# Pi_BISS_422_485.net
KiCad netlist of a schematic drawn in Altium Designer
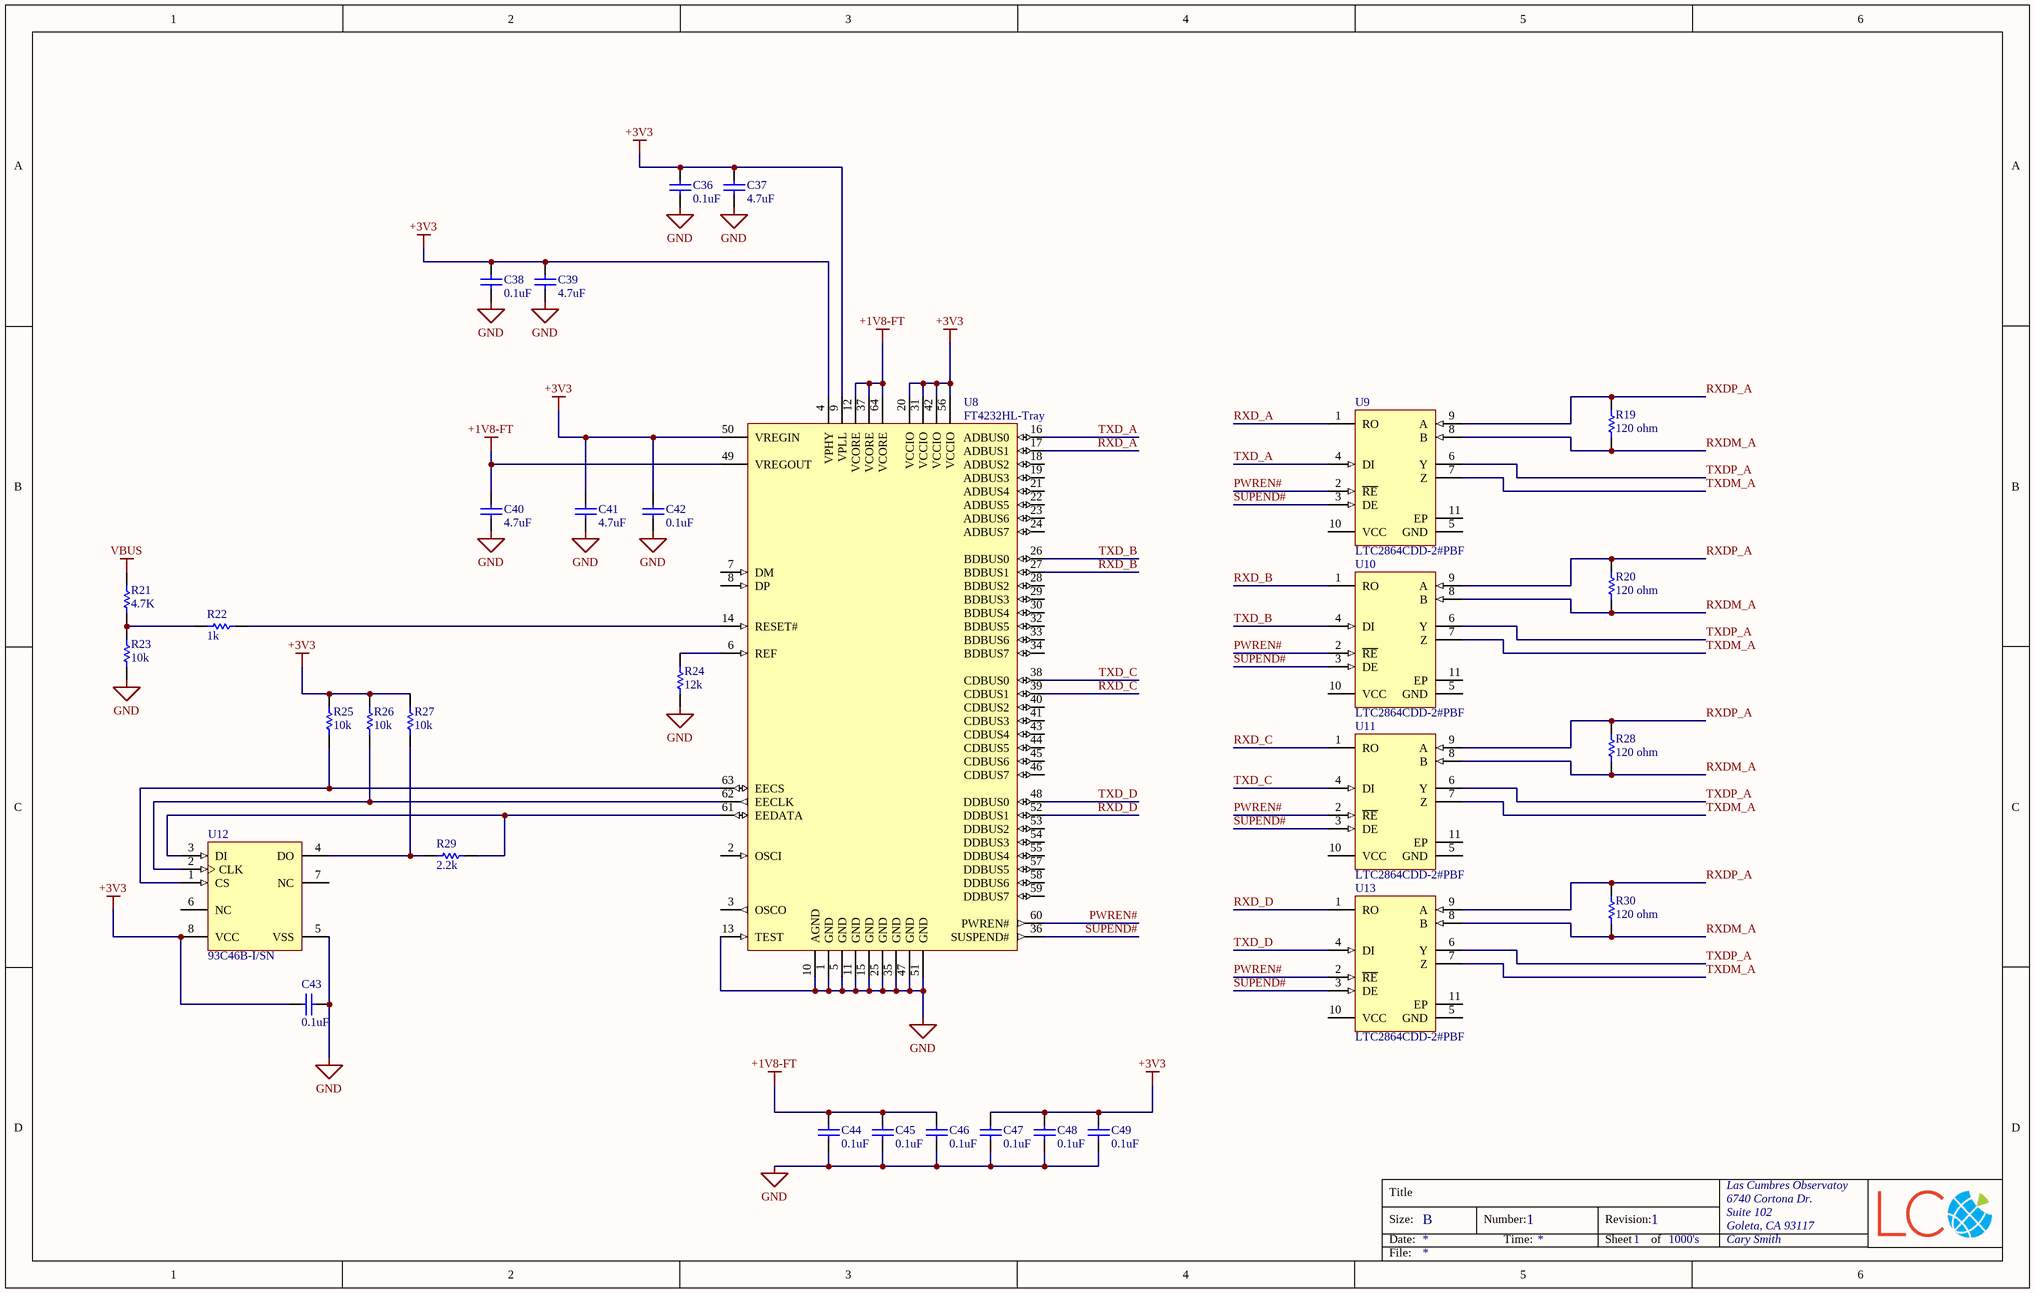
[diagram p0: Pi_BISS_422_485.SchDoc]

(export (version "E")
  (design (tool "Eeschema 10.0.6"))
  (components
    (comp (ref "C36")
      (value "0.1uF")
      (footprint "CAPC1005X55X25ML05T10")
      (description "VJ0402G104KXQCW1BC")
      (fields (field (name "MANUFACTURER") "Vitramon"))
      (libsource (lib "Altium Content Vault") (part "CAP"))
    )
    (comp (ref "C37")
      (value "4.7uF")
      (footprint "CAPC1608X90X35ML10T15")
      (fields (field (name "PARTNUMBER") "GRM188R60J475KE19D") (field (name "TOLERANCE") "10%"))
      (libsource (lib "Altium Content Vault") (part "CAP-NP-2"))
    )
    (comp (ref "C38")
      (value "0.1uF")
      (footprint "CAPC1005X55X25ML05T10")
      (description "VJ0402G104KXQCW1BC")
      (fields (field (name "MANUFACTURER") "Vitramon"))
      (libsource (lib "Altium Content Vault") (part "CAP"))
    )
    (comp (ref "C39")
      (value "4.7uF")
      (footprint "CAPC1608X90X35ML10T15")
      (fields (field (name "PARTNUMBER") "GRM188R60J475KE19D") (field (name "TOLERANCE") "10%"))
      (libsource (lib "Altium Content Vault") (part "CAP-NP-2"))
    )
    (comp (ref "C40")
      (value "4.7uF")
      (footprint "CAPC1608X90X35ML10T15")
      (fields (field (name "PARTNUMBER") "GRM188R60J475KE19D") (field (name "TOLERANCE") "10%"))
      (libsource (lib "Altium Content Vault") (part "CAP-NP-2"))
    )
    (comp (ref "C41")
      (value "4.7uF")
      (footprint "CAPC1608X90X35ML10T15")
      (fields (field (name "PARTNUMBER") "GRM188R60J475KE19D") (field (name "TOLERANCE") "10%"))
      (libsource (lib "Altium Content Vault") (part "CAP-NP-2"))
    )
    (comp (ref "C42")
      (value "0.1uF")
      (footprint "CAPC1005X55X25ML05T10")
      (description "VJ0402G104KXQCW1BC")
      (fields (field (name "MANUFACTURER") "Vitramon"))
      (libsource (lib "Altium Content Vault") (part "CAP"))
    )
    (comp (ref "C43")
      (value "0.1uF")
      (footprint "CAPC1005X55X25ML05T10")
      (description "VJ0402G104KXQCW1BC")
      (fields (field (name "MANUFACTURER") "Vitramon"))
      (libsource (lib "Altium Content Vault") (part "CAP"))
    )
    (comp (ref "C44")
      (value "0.1uF")
      (footprint "CAPC1005X55X25ML05T10")
      (description "VJ0402G104KXQCW1BC")
      (fields (field (name "MANUFACTURER") "Vitramon"))
      (libsource (lib "Altium Content Vault") (part "CAP"))
    )
    (comp (ref "C45")
      (value "0.1uF")
      (footprint "CAPC1005X55X25ML05T10")
      (description "VJ0402G104KXQCW1BC")
      (fields (field (name "MANUFACTURER") "Vitramon"))
      (libsource (lib "Altium Content Vault") (part "CAP"))
    )
    (comp (ref "C46")
      (value "0.1uF")
      (footprint "CAPC1005X55X25ML05T10")
      (description "VJ0402G104KXQCW1BC")
      (fields (field (name "MANUFACTURER") "Vitramon"))
      (libsource (lib "Altium Content Vault") (part "CAP"))
    )
    (comp (ref "C47")
      (value "0.1uF")
      (footprint "CAPC1005X55X25ML05T10")
      (description "VJ0402G104KXQCW1BC")
      (fields (field (name "MANUFACTURER") "Vitramon"))
      (libsource (lib "Altium Content Vault") (part "CAP"))
    )
    (comp (ref "C48")
      (value "0.1uF")
      (footprint "CAPC1005X55X25ML05T10")
      (description "VJ0402G104KXQCW1BC")
      (fields (field (name "MANUFACTURER") "Vitramon"))
      (libsource (lib "Altium Content Vault") (part "CAP"))
    )
    (comp (ref "C49")
      (value "0.1uF")
      (footprint "CAPC1005X55X25ML05T10")
      (description "VJ0402G104KXQCW1BC")
      (fields (field (name "MANUFACTURER") "Vitramon"))
      (libsource (lib "Altium Content Vault") (part "CAP"))
    )
    (comp (ref "R19")
      (value "120 ohm")
      (footprint "RESC3216X60X45ML10T20")
      (description "CRCW1206120RJNEA")
      (fields (field (name "MANUFACTURER") "Vishay Dale"))
      (libsource (lib "Altium Content Vault") (part "RES"))
    )
    (comp (ref "R20")
      (value "120 ohm")
      (footprint "RESC3216X60X45ML10T20")
      (description "CRCW1206120RJNEA")
      (fields (field (name "MANUFACTURER") "Vishay Dale"))
      (libsource (lib "Altium Content Vault") (part "RES"))
    )
    (comp (ref "R21")
      (value "4.7K")
      (footprint "RESC1005X40X25ML05T05")
      (fields (field (name "PARTNUMBER") "CRCW04024K70FKED") (field (name "TOLERANCE") "1%"))
      (libsource (lib "Altium Content Vault") (part "RES"))
    )
    (comp (ref "R22")
      (value "1k")
      (footprint "RESC1005X40X25LL05T10")
      (description "CRCW04021K00FKEDHP")
      (fields (field (name "MANUFACTURER") "Vishay Dale"))
      (libsource (lib "Altium Content Vault") (part "RES"))
    )
    (comp (ref "R23")
      (value "10k")
      (footprint "RESC1005X40X25NL05T05")
      (description "CRCW040210K0FKED")
      (fields (field (name "MANUFACTURER") "Vishay Dale"))
      (libsource (lib "Altium Content Vault") (part "RES"))
    )
    (comp (ref "R24")
      (value "12k")
      (footprint "RESC1005X40X25NL05T05")
      (description "CRCW040212K0FKED")
      (fields (field (name "MANUFACTURER") "Vishay Dale"))
      (libsource (lib "Altium Content Vault") (part "RES"))
    )
    (comp (ref "R25")
      (value "10k")
      (footprint "RESC1005X40X25NL05T05")
      (description "CRCW040210K0FKED")
      (fields (field (name "MANUFACTURER") "Vishay Dale"))
      (libsource (lib "Altium Content Vault") (part "RES"))
    )
    (comp (ref "R26")
      (value "10k")
      (footprint "RESC1005X40X25NL05T05")
      (description "CRCW040210K0FKED")
      (fields (field (name "MANUFACTURER") "Vishay Dale"))
      (libsource (lib "Altium Content Vault") (part "RES"))
    )
    (comp (ref "R27")
      (value "10k")
      (footprint "RESC1005X40X25NL05T05")
      (description "CRCW040210K0FKED")
      (fields (field (name "MANUFACTURER") "Vishay Dale"))
      (libsource (lib "Altium Content Vault") (part "RES"))
    )
    (comp (ref "R28")
      (value "120 ohm")
      (footprint "RESC3216X60X45ML10T20")
      (description "CRCW1206120RJNEA")
      (fields (field (name "MANUFACTURER") "Vishay Dale"))
      (libsource (lib "Altium Content Vault") (part "RES"))
    )
    (comp (ref "R29")
      (value "2.2k")
      (footprint "RESC1005X40X25LL10T10")
      (description "RK73B1ETTP222J")
      (fields (field (name "MANUFACTURER") "KOA Speer"))
      (libsource (lib "Altium Content Vault") (part "RES"))
    )
    (comp (ref "R30")
      (value "120 ohm")
      (footprint "RESC3216X60X45ML10T20")
      (description "CRCW1206120RJNEA")
      (fields (field (name "MANUFACTURER") "Vishay Dale"))
      (libsource (lib "Altium Content Vault") (part "RES"))
    )
    (comp (ref "U8")
      (value "FT4232HL-Tray")
      (footprint "LQFP-64_M")
      (description "Quad High Speed USB To Multipurpose UART/MPSSE IC, 64-pin LQFP, Tray")
      (fields (field (name "MANUFACTURER") "FTDI"))
      (libsource (lib "Altium Content Vault") (part "COM-UART-FT4232H-LQFP64"))
    )
    (comp (ref "U9")
      (value "LTC2864CDD-2#PBF")
      (footprint "LT-DD-10_V")
      (fields (field (name "MANUFACTURER") "Linear Technology"))
      (libsource (lib "Altium Content Vault") (part "LT-LTC2864-DD-10"))
    )
    (comp (ref "U10")
      (value "LTC2864CDD-2#PBF")
      (footprint "LT-DD-10_V")
      (fields (field (name "MANUFACTURER") "Linear Technology"))
      (libsource (lib "Altium Content Vault") (part "LT-LTC2864-DD-10"))
    )
    (comp (ref "U11")
      (value "LTC2864CDD-2#PBF")
      (footprint "LT-DD-10_V")
      (fields (field (name "MANUFACTURER") "Linear Technology"))
      (libsource (lib "Altium Content Vault") (part "LT-LTC2864-DD-10"))
    )
    (comp (ref "U12")
      (value "93C46B-I/SN")
      (footprint "SOIC-SN8_M")
      (description "1K, 64x16-bit, 5.0V Microwire Serial EEPROM, 8-Pin SOIC 150mil, Industrial Temperature")
      (libsource (lib "Altium Content Vault") (part "MEM-SEEPROM-93AA46B-P-8"))
    )
    (comp (ref "U13")
      (value "LTC2864CDD-2#PBF")
      (footprint "LT-DD-10_V")
      (fields (field (name "MANUFACTURER") "Linear Technology"))
      (libsource (lib "Altium Content Vault") (part "LT-LTC2864-DD-10"))
    )
  )
  (nets
    (net (code "1") (name "+1V8-FT") (class "Default")
      (node (ref "C40") (pin "2") (pinfunction "2_2") (pintype "passive"))
      (node (ref "C44") (pin "1") (pinfunction "1_1") (pintype "passive"))
      (node (ref "C45") (pin "1") (pinfunction "1_1") (pintype "passive"))
      (node (ref "C46") (pin "1") (pinfunction "1_1") (pintype "passive"))
      (node (ref "U8") (pin "12") (pinfunction "VCORE_12") (pintype "power_in"))
      (node (ref "U8") (pin "37") (pinfunction "VCORE_37") (pintype "power_in"))
      (node (ref "U8") (pin "49") (pinfunction "VREGOUT_49") (pintype "power_in"))
      (node (ref "U8") (pin "64") (pinfunction "VCORE_64") (pintype "power_in"))
    )
    (net (code "2") (name "+3V3") (class "Default")
      (node (ref "C36") (pin "1") (pinfunction "1_1") (pintype "passive"))
      (node (ref "C37") (pin "2") (pinfunction "2_2") (pintype "passive"))
      (node (ref "C38") (pin "1") (pinfunction "1_1") (pintype "passive"))
      (node (ref "C39") (pin "2") (pinfunction "2_2") (pintype "passive"))
      (node (ref "C41") (pin "2") (pinfunction "2_2") (pintype "passive"))
      (node (ref "C42") (pin "1") (pinfunction "1_1") (pintype "passive"))
      (node (ref "C43") (pin "2") (pinfunction "2_2") (pintype "passive"))
      (node (ref "C47") (pin "1") (pinfunction "1_1") (pintype "passive"))
      (node (ref "C48") (pin "1") (pinfunction "1_1") (pintype "passive"))
      (node (ref "C49") (pin "1") (pinfunction "1_1") (pintype "passive"))
      (node (ref "R25") (pin "2") (pinfunction "2_2") (pintype "passive"))
      (node (ref "R26") (pin "2") (pinfunction "2_2") (pintype "passive"))
      (node (ref "R27") (pin "2") (pinfunction "2_2") (pintype "passive"))
      (node (ref "U12") (pin "8") (pinfunction "VCC_8") (pintype "power_in"))
      (node (ref "U8") (pin "20") (pinfunction "VCCIO_20") (pintype "power_in"))
      (node (ref "U8") (pin "31") (pinfunction "VCCIO_31") (pintype "power_in"))
      (node (ref "U8") (pin "4") (pinfunction "VPHY_4") (pintype "power_in"))
      (node (ref "U8") (pin "42") (pinfunction "VCCIO_42") (pintype "power_in"))
      (node (ref "U8") (pin "50") (pinfunction "VREGIN_50") (pintype "power_in"))
      (node (ref "U8") (pin "56") (pinfunction "VCCIO_56") (pintype "power_in"))
      (node (ref "U8") (pin "9") (pinfunction "VPLL_9") (pintype "power_in"))
    )
    (net (code "3") (name "/PWREN#") (class "Default")
      (node (ref "U10") (pin "2") (pinfunction "~{RE}_2") (pintype "input"))
      (node (ref "U11") (pin "2") (pinfunction "~{RE}_2") (pintype "input"))
      (node (ref "U13") (pin "2") (pinfunction "~{RE}_2") (pintype "input"))
      (node (ref "U8") (pin "60") (pinfunction "PWREN#_60") (pintype "output"))
      (node (ref "U9") (pin "2") (pinfunction "~{RE}_2") (pintype "input"))
    )
    (net (code "4") (name "/RXDM_A") (class "Default")
      (node (ref "R19") (pin "1") (pinfunction "1_1") (pintype "passive"))
      (node (ref "R20") (pin "1") (pinfunction "1_1") (pintype "passive"))
      (node (ref "R28") (pin "1") (pinfunction "1_1") (pintype "passive"))
      (node (ref "R30") (pin "1") (pinfunction "1_1") (pintype "passive"))
      (node (ref "U10") (pin "8") (pinfunction "B_8") (pintype "input"))
      (node (ref "U11") (pin "8") (pinfunction "B_8") (pintype "input"))
      (node (ref "U13") (pin "8") (pinfunction "B_8") (pintype "input"))
      (node (ref "U9") (pin "8") (pinfunction "B_8") (pintype "input"))
    )
    (net (code "5") (name "/RXDP_A") (class "Default")
      (node (ref "R19") (pin "2") (pinfunction "2_2") (pintype "passive"))
      (node (ref "R20") (pin "2") (pinfunction "2_2") (pintype "passive"))
      (node (ref "R28") (pin "2") (pinfunction "2_2") (pintype "passive"))
      (node (ref "R30") (pin "2") (pinfunction "2_2") (pintype "passive"))
      (node (ref "U10") (pin "9") (pinfunction "A_9") (pintype "input"))
      (node (ref "U11") (pin "9") (pinfunction "A_9") (pintype "input"))
      (node (ref "U13") (pin "9") (pinfunction "A_9") (pintype "input"))
      (node (ref "U9") (pin "9") (pinfunction "A_9") (pintype "input"))
    )
    (net (code "6") (name "/RXD_A") (class "Default")
      (node (ref "U8") (pin "17") (pinfunction "ADBUS1_17") (pintype "bidirectional"))
      (node (ref "U9") (pin "1") (pinfunction "RO_1") (pintype "tri_state"))
    )
    (net (code "7") (name "/RXD_B") (class "Default")
      (node (ref "U10") (pin "1") (pinfunction "RO_1") (pintype "tri_state"))
      (node (ref "U8") (pin "27") (pinfunction "BDBUS1_27") (pintype "bidirectional"))
    )
    (net (code "8") (name "/RXD_C") (class "Default")
      (node (ref "U11") (pin "1") (pinfunction "RO_1") (pintype "tri_state"))
      (node (ref "U8") (pin "39") (pinfunction "CDBUS1_39") (pintype "bidirectional"))
    )
    (net (code "9") (name "/RXD_D") (class "Default")
      (node (ref "U13") (pin "1") (pinfunction "RO_1") (pintype "tri_state"))
      (node (ref "U8") (pin "52") (pinfunction "DDBUS1_52") (pintype "bidirectional"))
    )
    (net (code "10") (name "/SUPEND#") (class "Default")
      (node (ref "U10") (pin "3") (pinfunction "DE_3") (pintype "input"))
      (node (ref "U11") (pin "3") (pinfunction "DE_3") (pintype "input"))
      (node (ref "U13") (pin "3") (pinfunction "DE_3") (pintype "input"))
      (node (ref "U8") (pin "36") (pinfunction "SUSPEND#_36") (pintype "output"))
      (node (ref "U9") (pin "3") (pinfunction "DE_3") (pintype "input"))
    )
    (net (code "11") (name "/TXDM_A") (class "Default")
      (node (ref "U10") (pin "7") (pinfunction "Z_7") (pintype "tri_state"))
      (node (ref "U11") (pin "7") (pinfunction "Z_7") (pintype "tri_state"))
      (node (ref "U13") (pin "7") (pinfunction "Z_7") (pintype "tri_state"))
      (node (ref "U9") (pin "7") (pinfunction "Z_7") (pintype "tri_state"))
    )
    (net (code "12") (name "/TXDP_A") (class "Default")
      (node (ref "U10") (pin "6") (pinfunction "Y_6") (pintype "tri_state"))
      (node (ref "U11") (pin "6") (pinfunction "Y_6") (pintype "tri_state"))
      (node (ref "U13") (pin "6") (pinfunction "Y_6") (pintype "tri_state"))
      (node (ref "U9") (pin "6") (pinfunction "Y_6") (pintype "tri_state"))
    )
    (net (code "13") (name "/TXD_A") (class "Default")
      (node (ref "U8") (pin "16") (pinfunction "ADBUS0_16") (pintype "bidirectional"))
      (node (ref "U9") (pin "4") (pinfunction "DI_4") (pintype "input"))
    )
    (net (code "14") (name "/TXD_B") (class "Default")
      (node (ref "U10") (pin "4") (pinfunction "DI_4") (pintype "input"))
      (node (ref "U8") (pin "26") (pinfunction "BDBUS0_26") (pintype "bidirectional"))
    )
    (net (code "15") (name "/TXD_C") (class "Default")
      (node (ref "U11") (pin "4") (pinfunction "DI_4") (pintype "input"))
      (node (ref "U8") (pin "38") (pinfunction "CDBUS0_38") (pintype "bidirectional"))
    )
    (net (code "16") (name "/TXD_D") (class "Default")
      (node (ref "U13") (pin "4") (pinfunction "DI_4") (pintype "input"))
      (node (ref "U8") (pin "48") (pinfunction "DDBUS0_48") (pintype "bidirectional"))
    )
    (net (code "17") (name "GND") (class "Default")
      (node (ref "C36") (pin "2") (pinfunction "2_2") (pintype "passive"))
      (node (ref "C37") (pin "1") (pinfunction "1_1") (pintype "passive"))
      (node (ref "C38") (pin "2") (pinfunction "2_2") (pintype "passive"))
      (node (ref "C39") (pin "1") (pinfunction "1_1") (pintype "passive"))
      (node (ref "C40") (pin "1") (pinfunction "1_1") (pintype "passive"))
      (node (ref "C41") (pin "1") (pinfunction "1_1") (pintype "passive"))
      (node (ref "C42") (pin "2") (pinfunction "2_2") (pintype "passive"))
      (node (ref "C43") (pin "1") (pinfunction "1_1") (pintype "passive"))
      (node (ref "C44") (pin "2") (pinfunction "2_2") (pintype "passive"))
      (node (ref "C45") (pin "2") (pinfunction "2_2") (pintype "passive"))
      (node (ref "C46") (pin "2") (pinfunction "2_2") (pintype "passive"))
      (node (ref "C47") (pin "2") (pinfunction "2_2") (pintype "passive"))
      (node (ref "C48") (pin "2") (pinfunction "2_2") (pintype "passive"))
      (node (ref "C49") (pin "2") (pinfunction "2_2") (pintype "passive"))
      (node (ref "R23") (pin "1") (pinfunction "1_1") (pintype "passive"))
      (node (ref "R24") (pin "1") (pinfunction "1_1") (pintype "passive"))
      (node (ref "U12") (pin "5") (pinfunction "VSS_5") (pintype "power_in"))
      (node (ref "U8") (pin "1") (pinfunction "GND_1") (pintype "power_in"))
      (node (ref "U8") (pin "10") (pinfunction "AGND_10") (pintype "power_in"))
      (node (ref "U8") (pin "11") (pinfunction "GND_11") (pintype "power_in"))
      (node (ref "U8") (pin "13") (pinfunction "TEST_13") (pintype "input"))
      (node (ref "U8") (pin "15") (pinfunction "GND_15") (pintype "power_in"))
      (node (ref "U8") (pin "25") (pinfunction "GND_25") (pintype "power_in"))
      (node (ref "U8") (pin "35") (pinfunction "GND_35") (pintype "power_in"))
      (node (ref "U8") (pin "47") (pinfunction "GND_47") (pintype "power_in"))
      (node (ref "U8") (pin "5") (pinfunction "GND_5") (pintype "power_in"))
      (node (ref "U8") (pin "51") (pinfunction "GND_51") (pintype "power_in"))
    )
    (net (code "18") (name "Net-(R21-Pad1)") (class "Default")
      (node (ref "R21") (pin "1") (pinfunction "1_1") (pintype "passive"))
      (node (ref "R22") (pin "1") (pinfunction "1_1") (pintype "passive"))
      (node (ref "R23") (pin "2") (pinfunction "2_2") (pintype "passive"))
    )
    (net (code "19") (name "Net-(U8-REF)") (class "Default")
      (node (ref "R24") (pin "2") (pinfunction "2_2") (pintype "passive"))
      (node (ref "U8") (pin "6") (pinfunction "REF_6") (pintype "input"))
    )
    (net (code "20") (name "Net-(U8-RESET#)") (class "Default")
      (node (ref "R22") (pin "2") (pinfunction "2_2") (pintype "passive"))
      (node (ref "U8") (pin "14") (pinfunction "RESET#_14") (pintype "input"))
    )
    (net (code "21") (name "Net-(U12-CLK)") (class "Default")
      (node (ref "R26") (pin "1") (pinfunction "1_1") (pintype "passive"))
      (node (ref "U12") (pin "2") (pinfunction "CLK_2") (pintype "input"))
      (node (ref "U8") (pin "62") (pinfunction "EECLK_62") (pintype "output"))
    )
    (net (code "22") (name "Net-(U12-CS)") (class "Default")
      (node (ref "R25") (pin "1") (pinfunction "1_1") (pintype "passive"))
      (node (ref "U12") (pin "1") (pinfunction "CS_1") (pintype "input"))
      (node (ref "U8") (pin "63") (pinfunction "EECS_63") (pintype "bidirectional"))
    )
    (net (code "23") (name "Net-(U12-DI)") (class "Default")
      (node (ref "R29") (pin "2") (pinfunction "2_2") (pintype "passive"))
      (node (ref "U12") (pin "3") (pinfunction "DI_3") (pintype "input"))
      (node (ref "U8") (pin "61") (pinfunction "EEDATA_61") (pintype "bidirectional"))
    )
    (net (code "24") (name "Net-(U12-DO)") (class "Default")
      (node (ref "R27") (pin "1") (pinfunction "1_1") (pintype "passive"))
      (node (ref "R29") (pin "1") (pinfunction "1_1") (pintype "passive"))
      (node (ref "U12") (pin "4") (pinfunction "DO_4") (pintype "tri_state"))
    )
    (net (code "25") (name "VBUS") (class "Default")
      (node (ref "R21") (pin "2") (pinfunction "2_2") (pintype "passive"))
    )
    (net (code "26") (name "unconnected-(U8-ADBUS2-Pad18)") (class "Default")
      (node (ref "U8") (pin "18") (pinfunction "ADBUS2_18") (pintype "bidirectional"))
    )
    (net (code "27") (name "unconnected-(U8-ADBUS3-Pad19)") (class "Default")
      (node (ref "U8") (pin "19") (pinfunction "ADBUS3_19") (pintype "bidirectional"))
    )
    (net (code "28") (name "unconnected-(U8-ADBUS4-Pad21)") (class "Default")
      (node (ref "U8") (pin "21") (pinfunction "ADBUS4_21") (pintype "bidirectional"))
    )
    (net (code "29") (name "unconnected-(U8-ADBUS5-Pad22)") (class "Default")
      (node (ref "U8") (pin "22") (pinfunction "ADBUS5_22") (pintype "bidirectional"))
    )
    (net (code "30") (name "unconnected-(U8-ADBUS6-Pad23)") (class "Default")
      (node (ref "U8") (pin "23") (pinfunction "ADBUS6_23") (pintype "bidirectional"))
    )
    (net (code "31") (name "unconnected-(U8-ADBUS7-Pad24)") (class "Default")
      (node (ref "U8") (pin "24") (pinfunction "ADBUS7_24") (pintype "bidirectional"))
    )
    (net (code "32") (name "unconnected-(U8-BDBUS2-Pad28)") (class "Default")
      (node (ref "U8") (pin "28") (pinfunction "BDBUS2_28") (pintype "bidirectional"))
    )
    (net (code "33") (name "unconnected-(U8-BDBUS3-Pad29)") (class "Default")
      (node (ref "U8") (pin "29") (pinfunction "BDBUS3_29") (pintype "bidirectional"))
    )
    (net (code "34") (name "unconnected-(U8-BDBUS4-Pad30)") (class "Default")
      (node (ref "U8") (pin "30") (pinfunction "BDBUS4_30") (pintype "bidirectional"))
    )
    (net (code "35") (name "unconnected-(U8-BDBUS5-Pad32)") (class "Default")
      (node (ref "U8") (pin "32") (pinfunction "BDBUS5_32") (pintype "bidirectional"))
    )
    (net (code "36") (name "unconnected-(U8-BDBUS6-Pad33)") (class "Default")
      (node (ref "U8") (pin "33") (pinfunction "BDBUS6_33") (pintype "bidirectional"))
    )
    (net (code "37") (name "unconnected-(U8-BDBUS7-Pad34)") (class "Default")
      (node (ref "U8") (pin "34") (pinfunction "BDBUS7_34") (pintype "bidirectional"))
    )
    (net (code "38") (name "unconnected-(U8-CDBUS2-Pad40)") (class "Default")
      (node (ref "U8") (pin "40") (pinfunction "CDBUS2_40") (pintype "bidirectional"))
    )
    (net (code "39") (name "unconnected-(U8-CDBUS3-Pad41)") (class "Default")
      (node (ref "U8") (pin "41") (pinfunction "CDBUS3_41") (pintype "bidirectional"))
    )
    (net (code "40") (name "unconnected-(U8-CDBUS4-Pad43)") (class "Default")
      (node (ref "U8") (pin "43") (pinfunction "CDBUS4_43") (pintype "bidirectional"))
    )
    (net (code "41") (name "unconnected-(U8-CDBUS5-Pad44)") (class "Default")
      (node (ref "U8") (pin "44") (pinfunction "CDBUS5_44") (pintype "bidirectional"))
    )
    (net (code "42") (name "unconnected-(U8-CDBUS6-Pad45)") (class "Default")
      (node (ref "U8") (pin "45") (pinfunction "CDBUS6_45") (pintype "bidirectional"))
    )
    (net (code "43") (name "unconnected-(U8-CDBUS7-Pad46)") (class "Default")
      (node (ref "U8") (pin "46") (pinfunction "CDBUS7_46") (pintype "bidirectional"))
    )
    (net (code "44") (name "unconnected-(U8-DDBUS2-Pad53)") (class "Default")
      (node (ref "U8") (pin "53") (pinfunction "DDBUS2_53") (pintype "bidirectional"))
    )
    (net (code "45") (name "unconnected-(U8-DDBUS3-Pad54)") (class "Default")
      (node (ref "U8") (pin "54") (pinfunction "DDBUS3_54") (pintype "bidirectional"))
    )
    (net (code "46") (name "unconnected-(U8-DDBUS4-Pad55)") (class "Default")
      (node (ref "U8") (pin "55") (pinfunction "DDBUS4_55") (pintype "bidirectional"))
    )
    (net (code "47") (name "unconnected-(U8-DDBUS5-Pad57)") (class "Default")
      (node (ref "U8") (pin "57") (pinfunction "DDBUS5_57") (pintype "bidirectional"))
    )
    (net (code "48") (name "unconnected-(U8-DDBUS6-Pad58)") (class "Default")
      (node (ref "U8") (pin "58") (pinfunction "DDBUS6_58") (pintype "bidirectional"))
    )
    (net (code "49") (name "unconnected-(U8-DDBUS7-Pad59)") (class "Default")
      (node (ref "U8") (pin "59") (pinfunction "DDBUS7_59") (pintype "bidirectional"))
    )
    (net (code "50") (name "unconnected-(U8-DM-Pad7)") (class "Default")
      (node (ref "U8") (pin "7") (pinfunction "DM_7") (pintype "input"))
    )
    (net (code "51") (name "unconnected-(U8-DP-Pad8)") (class "Default")
      (node (ref "U8") (pin "8") (pinfunction "DP_8") (pintype "input"))
    )
    (net (code "52") (name "unconnected-(U8-OSCI-Pad2)") (class "Default")
      (node (ref "U8") (pin "2") (pinfunction "OSCI_2") (pintype "input"))
    )
    (net (code "53") (name "unconnected-(U8-OSCO-Pad3)") (class "Default")
      (node (ref "U8") (pin "3") (pinfunction "OSCO_3") (pintype "output"))
    )
    (net (code "54") (name "unconnected-(U9-EP-Pad11)") (class "Default")
      (node (ref "U9") (pin "11") (pinfunction "EP_11") (pintype "power_in"))
    )
    (net (code "55") (name "unconnected-(U9-GND-Pad5)") (class "Default")
      (node (ref "U9") (pin "5") (pinfunction "GND_5") (pintype "power_in"))
    )
    (net (code "56") (name "unconnected-(U9-VCC-Pad10)") (class "Default")
      (node (ref "U9") (pin "10") (pinfunction "VCC_10") (pintype "power_in"))
    )
    (net (code "57") (name "unconnected-(U10-EP-Pad11)") (class "Default")
      (node (ref "U10") (pin "11") (pinfunction "EP_11") (pintype "power_in"))
    )
    (net (code "58") (name "unconnected-(U10-GND-Pad5)") (class "Default")
      (node (ref "U10") (pin "5") (pinfunction "GND_5") (pintype "power_in"))
    )
    (net (code "59") (name "unconnected-(U10-VCC-Pad10)") (class "Default")
      (node (ref "U10") (pin "10") (pinfunction "VCC_10") (pintype "power_in"))
    )
    (net (code "60") (name "unconnected-(U11-EP-Pad11)") (class "Default")
      (node (ref "U11") (pin "11") (pinfunction "EP_11") (pintype "power_in"))
    )
    (net (code "61") (name "unconnected-(U11-GND-Pad5)") (class "Default")
      (node (ref "U11") (pin "5") (pinfunction "GND_5") (pintype "power_in"))
    )
    (net (code "62") (name "unconnected-(U11-VCC-Pad10)") (class "Default")
      (node (ref "U11") (pin "10") (pinfunction "VCC_10") (pintype "power_in"))
    )
    (net (code "63") (name "unconnected-(U12-NC-Pad6)") (class "Default")
      (node (ref "U12") (pin "6") (pinfunction "NC_6") (pintype "passive"))
    )
    (net (code "64") (name "unconnected-(U12-NC-Pad7)") (class "Default")
      (node (ref "U12") (pin "7") (pinfunction "NC_7") (pintype "passive"))
    )
    (net (code "65") (name "unconnected-(U13-EP-Pad11)") (class "Default")
      (node (ref "U13") (pin "11") (pinfunction "EP_11") (pintype "power_in"))
    )
    (net (code "66") (name "unconnected-(U13-GND-Pad5)") (class "Default")
      (node (ref "U13") (pin "5") (pinfunction "GND_5") (pintype "power_in"))
    )
    (net (code "67") (name "unconnected-(U13-VCC-Pad10)") (class "Default")
      (node (ref "U13") (pin "10") (pinfunction "VCC_10") (pintype "power_in"))
    )
  )
)
